# perifericos.net
KiCad netlist of a schematic drawn in Altium Designer
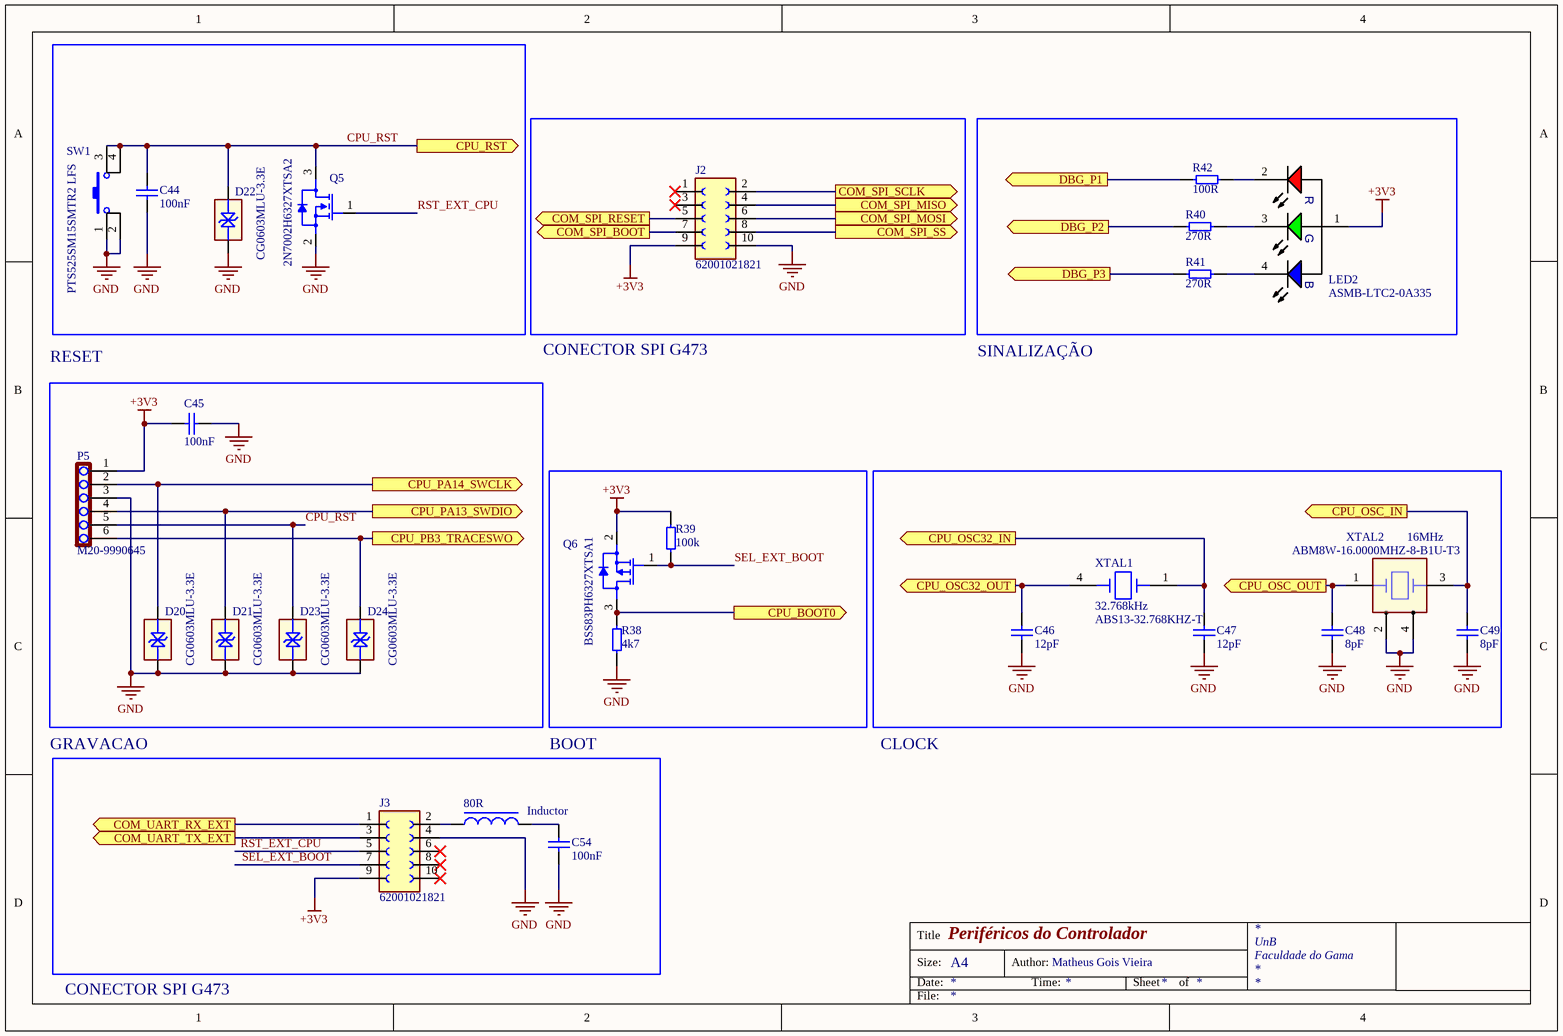
[diagram p0: perifericos.SchDoc]

(export (version "E")
  (design (tool "Eeschema 10.0.6"))
  (components
    (comp (ref "80R")
      (value "Inductor")
      (footprint "R1608[0603]")
      (libsource (lib "Basic Library") (part "L"))
    )
    (comp (ref "C44")
      (value "100nF")
      (footprint "0603")
      (description "Capacitor Ceramic 100nF 20% 50V 0603 (1608 Metric) X7R")
      (fields (field (name "TOLERANCE") "20%") (field (name "MPN") "C0603C104M5RACTU"))
      (libsource (lib "Biblioteca_Clamper") (part "CAP CER SMD-0603 100nF - 50V"))
    )
    (comp (ref "C45")
      (value "100nF")
      (footprint "0603")
      (description "Capacitor Ceramic 100nF 20% 50V 0603 (1608 Metric) X7R")
      (fields (field (name "TOLERANCE") "20%") (field (name "MPN") "C0603C104M5RACTU"))
      (libsource (lib "Biblioteca_Clamper") (part "CAP CER SMD-0603 100nF - 50V"))
    )
    (comp (ref "C46")
      (value "12pF")
      (footprint "0603")
      (description "Capacitor Ceramic 12pF 10% 50V 0603 (1608 Metric) C0G (NP0)")
      (fields (field (name "VOLTAGE") "50V") (field (name "TOLERANCE") "10%"))
      (libsource (lib "Biblioteca_Clamper") (part "CAP CER SMD-0603 12pF - 50V"))
    )
    (comp (ref "C47")
      (value "12pF")
      (footprint "0603")
      (description "Capacitor Ceramic 12pF 10% 50V 0603 (1608 Metric) C0G (NP0)")
      (fields (field (name "VOLTAGE") "50V") (field (name "TOLERANCE") "10%"))
      (libsource (lib "Biblioteca_Clamper") (part "CAP CER SMD-0603 12pF - 50V"))
    )
    (comp (ref "C48")
      (value "8pF")
      (footprint "0603")
      (description "Capacitor Ceramic 8pF 50V 0603 (1608 Metric) C0G (NP0)")
      (fields (field (name "MPN") "CC0603DRNPO9BN8R0") (field (name "MANUFACTURER") "Yageo"))
      (libsource (lib "Biblioteca_Clamper") (part "CAP CER SMD-0603 8pF - 50V"))
    )
    (comp (ref "C49")
      (value "8pF")
      (footprint "0603")
      (description "Capacitor Ceramic 8pF 50V 0603 (1608 Metric) C0G (NP0)")
      (fields (field (name "MPN") "CC0603DRNPO9BN8R0") (field (name "MANUFACTURER") "Yageo"))
      (libsource (lib "Biblioteca_Clamper") (part "CAP CER SMD-0603 8pF - 50V"))
    )
    (comp (ref "C54")
      (value "100nF")
      (footprint "0603")
      (description "Capacitor Ceramic 100nF 20% 50V 0603 (1608 Metric) X7R")
      (fields (field (name "TOLERANCE") "20%") (field (name "MPN") "C0603C104M5RACTU"))
      (libsource (lib "Biblioteca_Clamper") (part "CAP CER SMD-0603 100nF - 50V"))
    )
    (comp (ref "D20")
      (value "CG0603MLU-3.3E")
      (footprint "DIODE-0603")
      (description "TVS DIODE 3.3V 25V 0603 (1608 metric)")
      (fields (field (name "MANUFACTURER") "Bourns") (field (name "VOLTAGE") "3.3V"))
      (libsource (lib "Biblioteca_Clamper") (part "DIODE SMD CG0603MLU-3.3E"))
    )
    (comp (ref "D21")
      (value "CG0603MLU-3.3E")
      (footprint "DIODE-0603")
      (description "TVS DIODE 3.3V 25V 0603 (1608 metric)")
      (fields (field (name "MANUFACTURER") "Bourns") (field (name "VOLTAGE") "3.3V"))
      (libsource (lib "Biblioteca_Clamper") (part "DIODE SMD CG0603MLU-3.3E"))
    )
    (comp (ref "D22")
      (value "CG0603MLU-3.3E")
      (footprint "DIODE-0603")
      (description "TVS DIODE 3.3V 25V 0603 (1608 metric)")
      (fields (field (name "MANUFACTURER") "Bourns") (field (name "VOLTAGE") "3.3V"))
      (libsource (lib "Biblioteca_Clamper") (part "DIODE SMD CG0603MLU-3.3E"))
    )
    (comp (ref "D23")
      (value "CG0603MLU-3.3E")
      (footprint "DIODE-0603")
      (description "TVS DIODE 3.3V 25V 0603 (1608 metric)")
      (fields (field (name "MANUFACTURER") "Bourns") (field (name "VOLTAGE") "3.3V"))
      (libsource (lib "Biblioteca_Clamper") (part "DIODE SMD CG0603MLU-3.3E"))
    )
    (comp (ref "D24")
      (value "CG0603MLU-3.3E")
      (footprint "DIODE-0603")
      (description "TVS DIODE 3.3V 25V 0603 (1608 metric)")
      (fields (field (name "MANUFACTURER") "Bourns") (field (name "VOLTAGE") "3.3V"))
      (libsource (lib "Biblioteca_Clamper") (part "DIODE SMD CG0603MLU-3.3E"))
    )
    (comp (ref "J2")
      (value "62001021821")
      (footprint "62001021821")
      (fields (field (name "MF") "WÃ¼rth Elektronik"))
      (libsource (lib "62001021821") (part "62001021821"))
    )
    (comp (ref "J3")
      (value "62001021821")
      (footprint "62001021821")
      (fields (field (name "MF") "WÃ¼rth Elektronik"))
      (libsource (lib "62001021821") (part "62001021821"))
    )
    (comp (ref "LED2")
      (value "ASMB-LTC2-0A335")
      (footprint "ASMB-LTC2-0A335")
      (description "LED SMD-2121 PLCC4 RGB - 70mcd Red (2V), 300mcd Green (2.7V), 50mcd Blue (2.7V)")
      (fields (field (name "MANUFACTURER") "Broadcom Limited"))
      (libsource (lib "Biblioteca_Clamper") (part "LED2 SMD-2121 PLCC4 RGB AComum"))
    )
    (comp (ref "P5")
      (value "M20-9990645")
      (footprint "HDR1X6-2.54MM")
      (description "Header, 6-Pin, 2.54mm, PCB")
      (fields (field (name "MANUFACTURER") "HARWIN"))
      (libsource (lib "Biblioteca_Clamper") (part "HEADER 1x6 PTH"))
    )
    (comp (ref "Q5")
      (value "2N7002H6327XTSA2")
      (footprint "CI-SOT-23")
      (description "MOSFET N-CH 60V 300mA SOT23-3")
      (fields (field (name "MANUFACTURER") "Infineon"))
      (libsource (lib "Biblioteca_Clamper") (part "MOSFET N-CHANNEL 2N7002"))
    )
    (comp (ref "Q6")
      (value "BSS83PH6327XTSA1")
      (footprint "CI-SOT-23")
      (description "MOSFET P-CH 60V 330mA SOT23-3")
      (fields (field (name "MANUFACTURER") "Infineon"))
      (libsource (lib "Biblioteca_Clamper") (part "MOSFET P-CHANNEL BSS83P"))
    )
    (comp (ref "R38")
      (value "4k7")
      (footprint "0603")
      (description "Resistor Thick Film 4k7 0.5% 0.063W, 1/16W 0603 (1608 metric) +/- 25 PPM / K")
      (fields (field (name "MPN") "RR0816P-472-D") (field (name "MANUFACTURER") "Susumu"))
      (libsource (lib "Biblioteca_Clamper") (part "RES SMD-0603 4k7 0.5% 1/16W"))
    )
    (comp (ref "R39")
      (value "100k")
      (footprint "0603")
      (description "Resistor Thick Film 100k 1% 0.1W, 1/10W 0603 (1608 metric) +/- 100 PPM / K")
      (fields (field (name "TOLERANCE") "1%") (field (name "MPN") "CRCW0603100KFKEA"))
      (libsource (lib "Biblioteca_Clamper") (part "RES SMD-0603 100k 1% 1/10W"))
    )
    (comp (ref "R40")
      (value "270R")
      (footprint "0603")
      (fields
        (field (name "TOLERANCE") "±1%")
        (field (name "MPN") "RMCF0603FT270R")
        (field (name "MANUFACTURER") "Stackpole Electronics Inc")
      )
      (libsource (lib "Biblioteca_Clamper") (part "RES SMD-0603 270R 1% 1/10W"))
    )
    (comp (ref "R41")
      (value "270R")
      (footprint "0603")
      (fields
        (field (name "TOLERANCE") "±1%")
        (field (name "MPN") "RMCF0603FT270R")
        (field (name "MANUFACTURER") "Stackpole Electronics Inc")
      )
      (libsource (lib "Biblioteca_Clamper") (part "RES SMD-0603 270R 1% 1/10W"))
    )
    (comp (ref "R42")
      (value "100R")
      (footprint "0603")
      (description "Resistor Thick Film 100R 1% 0.1W, 1/10W 0603 (1608 metric) +/- 100 PPM / K")
      (fields (field (name "TOLERANCE") "1%") (field (name "MPN") "RC0603FR-07100RL"))
      (libsource (lib "Biblioteca_Clamper") (part "RES SMD-0603 100R 1% 1/10W"))
    )
    (comp (ref "SW1")
      (value "PTS525SM15SMTR2 LFS")
      (footprint "SWTCH")
      (description "Chave pushbuttom NA polo simples SMD")
      (fields (field (name "MANUFACTURER") "C&K") (field (name "Comment") "Tact Switch"))
      (libsource (lib "Biblioteca_Clamper") (part "Tact Switch"))
    )
    (comp (ref "XTAL1")
      (value "32.768kHz")
      (footprint "XTAL4P_ABS13")
      (description "Crystal 32.768kHz 20PPM SMD")
      (fields
        (field (name "TOLERANCE") "20PPM")
        (field (name "MANUFACTURER") "Abracon")
        (field (name "MPN") "ABS13-32.768KHZ-T")
      )
      (libsource (lib "Biblioteca_Clamper") (part "XTAL-ABS13-32.768kHz"))
    )
    (comp (ref "XTAL2")
      (value "16MHz")
      (footprint "XTAL4P")
      (description "Crystal 16MHz 10PPM SMD")
      (fields
        (field (name "TOLERANCE") "10PPM")
        (field (name "MANUFACTURER") "Abracon")
        (field (name "MPN") "ABM8W-16.0000MHZ-8-B1U-T3")
      )
      (libsource (lib "Biblioteca_Clamper") (part "XTAL-ABM8W-16MHz"))
    )
  )
  (nets
    (net (code "1") (name "+3V3") (class "Default")
      (node (ref "C45") (pin "1") (pinfunction "1_1") (pintype "passive"))
      (node (ref "J2") (pin "9") (pinfunction "5_9") (pintype "passive"))
      (node (ref "J3") (pin "9") (pinfunction "5_9") (pintype "passive"))
      (node (ref "LED2") (pin "1") (pinfunction "A_1") (pintype "passive"))
      (node (ref "P5") (pin "1") (pinfunction "1_1") (pintype "passive"))
      (node (ref "Q6") (pin "2") (pinfunction "S_2") (pintype "passive"))
      (node (ref "R39") (pin "2") (pinfunction "2_2") (pintype "passive"))
    )
    (net (code "2") (name "/COM_SPI_BOOT") (class "Default")
      (node (ref "J2") (pin "7") (pinfunction "4_7") (pintype "passive"))
    )
    (net (code "3") (name "/COM_SPI_MISO") (class "Default")
      (node (ref "J2") (pin "4") (pinfunction "9_4") (pintype "passive"))
    )
    (net (code "4") (name "/COM_SPI_MOSI") (class "Default")
      (node (ref "J2") (pin "6") (pinfunction "8_6") (pintype "passive"))
    )
    (net (code "5") (name "/COM_SPI_RESET") (class "Default")
      (node (ref "J2") (pin "5") (pinfunction "3_5") (pintype "passive"))
    )
    (net (code "6") (name "/COM_SPI_SCLK") (class "Default")
      (node (ref "J2") (pin "2") (pinfunction "10_2") (pintype "passive"))
    )
    (net (code "7") (name "/COM_SPI_SS") (class "Default")
      (node (ref "J2") (pin "8") (pinfunction "7_8") (pintype "passive"))
    )
    (net (code "8") (name "/COM_UART_RX_EXT") (class "Default")
      (node (ref "J3") (pin "1") (pinfunction "1_1") (pintype "passive"))
    )
    (net (code "9") (name "/COM_UART_TX_EXT") (class "Default")
      (node (ref "J3") (pin "3") (pinfunction "2_3") (pintype "passive"))
    )
    (net (code "10") (name "/CPU_BOOT0") (class "Default")
      (node (ref "Q6") (pin "3") (pinfunction "D_3") (pintype "passive"))
      (node (ref "R38") (pin "2") (pinfunction "2_2") (pintype "passive"))
    )
    (net (code "11") (name "/CPU_OSC32_IN") (class "Default")
      (node (ref "C47") (pin "2") (pinfunction "2_2") (pintype "passive"))
      (node (ref "XTAL1") (pin "1") (pinfunction "1_1") (pintype "passive"))
    )
    (net (code "12") (name "/CPU_OSC32_OUT") (class "Default")
      (node (ref "C46") (pin "2") (pinfunction "2_2") (pintype "passive"))
      (node (ref "XTAL1") (pin "4") (pinfunction "4_4") (pintype "passive"))
    )
    (net (code "13") (name "/CPU_OSC_IN") (class "Default")
      (node (ref "C49") (pin "2") (pinfunction "2_2") (pintype "passive"))
      (node (ref "XTAL2") (pin "3") (pinfunction "3_3") (pintype "passive"))
    )
    (net (code "14") (name "/CPU_OSC_OUT") (class "Default")
      (node (ref "C48") (pin "2") (pinfunction "2_2") (pintype "passive"))
      (node (ref "XTAL2") (pin "1") (pinfunction "1_1") (pintype "passive"))
    )
    (net (code "15") (name "/CPU_PA13_SWDIO") (class "Default")
      (node (ref "D21") (pin "2") (pintype "passive"))
      (node (ref "P5") (pin "4") (pinfunction "4_4") (pintype "passive"))
    )
    (net (code "16") (name "/CPU_PA14_SWCLK") (class "Default")
      (node (ref "D20") (pin "2") (pintype "passive"))
      (node (ref "P5") (pin "2") (pinfunction "2_2") (pintype "passive"))
    )
    (net (code "17") (name "/CPU_PB3_TRACESWO") (class "Default")
      (node (ref "D24") (pin "2") (pintype "passive"))
      (node (ref "P5") (pin "6") (pinfunction "6_6") (pintype "passive"))
    )
    (net (code "18") (name "/CPU_RST") (class "Default")
      (node (ref "C44") (pin "1") (pinfunction "1_1") (pintype "passive"))
      (node (ref "D22") (pin "2") (pintype "passive"))
      (node (ref "D23") (pin "2") (pintype "passive"))
      (node (ref "P5") (pin "5") (pinfunction "5_5") (pintype "passive"))
      (node (ref "Q5") (pin "3") (pinfunction "D_3") (pintype "passive"))
      (node (ref "SW1") (pin "3") (pinfunction "3_3") (pintype "passive"))
      (node (ref "SW1") (pin "4") (pinfunction "4_4") (pintype "passive"))
    )
    (net (code "19") (name "/DBG_P1") (class "Default")
      (node (ref "R42") (pin "1") (pinfunction "1_1") (pintype "passive"))
    )
    (net (code "20") (name "/DBG_P2") (class "Default")
      (node (ref "R40") (pin "1") (pinfunction "1_1") (pintype "passive"))
    )
    (net (code "21") (name "/DBG_P3") (class "Default")
      (node (ref "R41") (pin "1") (pinfunction "1_1") (pintype "passive"))
    )
    (net (code "22") (name "/RST_EXT_CPU") (class "Default")
      (node (ref "J3") (pin "5") (pinfunction "3_5") (pintype "passive"))
      (node (ref "Q5") (pin "1") (pinfunction "G_1") (pintype "passive"))
    )
    (net (code "23") (name "/SEL_EXT_BOOT") (class "Default")
      (node (ref "J3") (pin "7") (pinfunction "4_7") (pintype "passive"))
      (node (ref "Q6") (pin "1") (pinfunction "G_1") (pintype "passive"))
      (node (ref "R39") (pin "1") (pinfunction "1_1") (pintype "passive"))
    )
    (net (code "24") (name "GND") (class "Default")
      (node (ref "C44") (pin "2") (pinfunction "2_2") (pintype "passive"))
      (node (ref "C45") (pin "2") (pinfunction "2_2") (pintype "passive"))
      (node (ref "C46") (pin "1") (pinfunction "1_1") (pintype "passive"))
      (node (ref "C47") (pin "1") (pinfunction "1_1") (pintype "passive"))
      (node (ref "C48") (pin "1") (pinfunction "1_1") (pintype "passive"))
      (node (ref "C49") (pin "1") (pinfunction "1_1") (pintype "passive"))
      (node (ref "C54") (pin "2") (pinfunction "2_2") (pintype "passive"))
      (node (ref "D20") (pin "1") (pintype "passive"))
      (node (ref "D21") (pin "1") (pintype "passive"))
      (node (ref "D22") (pin "1") (pintype "passive"))
      (node (ref "D23") (pin "1") (pintype "passive"))
      (node (ref "D24") (pin "1") (pintype "passive"))
      (node (ref "J2") (pin "10") (pinfunction "6_10") (pintype "passive"))
      (node (ref "J3") (pin "4") (pinfunction "9_4") (pintype "passive"))
      (node (ref "P5") (pin "3") (pinfunction "3_3") (pintype "passive"))
      (node (ref "Q5") (pin "2") (pinfunction "S_2") (pintype "passive"))
      (node (ref "R38") (pin "1") (pinfunction "1_1") (pintype "passive"))
      (node (ref "SW1") (pin "1") (pinfunction "1_1") (pintype "passive"))
      (node (ref "SW1") (pin "2") (pinfunction "2_2") (pintype "passive"))
      (node (ref "XTAL2") (pin "2") (pinfunction "GND_2") (pintype "power_in"))
      (node (ref "XTAL2") (pin "4") (pinfunction "GND_4") (pintype "power_in"))
    )
    (net (code "25") (name "Net-(80R-Pad2)") (class "Default")
      (node (ref "80R") (pin "2") (pinfunction "2_2") (pintype "passive"))
      (node (ref "C54") (pin "1") (pinfunction "1_1") (pintype "passive"))
    )
    (net (code "26") (name "Net-(J3-10)") (class "Default")
      (node (ref "80R") (pin "1") (pinfunction "1_1") (pintype "passive"))
      (node (ref "J3") (pin "2") (pinfunction "10_2") (pintype "passive"))
    )
    (net (code "27") (name "Net-(LED2-B)") (class "Default")
      (node (ref "LED2") (pin "4") (pinfunction "B_4") (pintype "passive"))
      (node (ref "R41") (pin "2") (pinfunction "2_2") (pintype "passive"))
    )
    (net (code "28") (name "Net-(LED2-G)") (class "Default")
      (node (ref "LED2") (pin "3") (pinfunction "G_3") (pintype "passive"))
      (node (ref "R40") (pin "2") (pinfunction "2_2") (pintype "passive"))
    )
    (net (code "29") (name "Net-(LED2-R)") (class "Default")
      (node (ref "LED2") (pin "2") (pinfunction "R_2") (pintype "passive"))
      (node (ref "R42") (pin "2") (pinfunction "2_2") (pintype "passive"))
    )
    (net (code "30") (name "unconnected-(J2-2-Pad3)") (class "Default")
      (node (ref "J2") (pin "3") (pinfunction "2_3") (pintype "passive+no_connect"))
    )
    (net (code "31") (name "unconnected-(J2-Pad1)") (class "Default")
      (node (ref "J2") (pin "1") (pinfunction "1_1") (pintype "passive+no_connect"))
    )
    (net (code "32") (name "unconnected-(J3-6-Pad10)") (class "Default")
      (node (ref "J3") (pin "10") (pinfunction "6_10") (pintype "passive+no_connect"))
    )
    (net (code "33") (name "unconnected-(J3-7-Pad8)") (class "Default")
      (node (ref "J3") (pin "8") (pinfunction "7_8") (pintype "passive+no_connect"))
    )
    (net (code "34") (name "unconnected-(J3-8-Pad6)") (class "Default")
      (node (ref "J3") (pin "6") (pinfunction "8_6") (pintype "passive+no_connect"))
    )
  )
)
